# OpAmp.net
KiCad netlist of a schematic drawn in Altium Designer
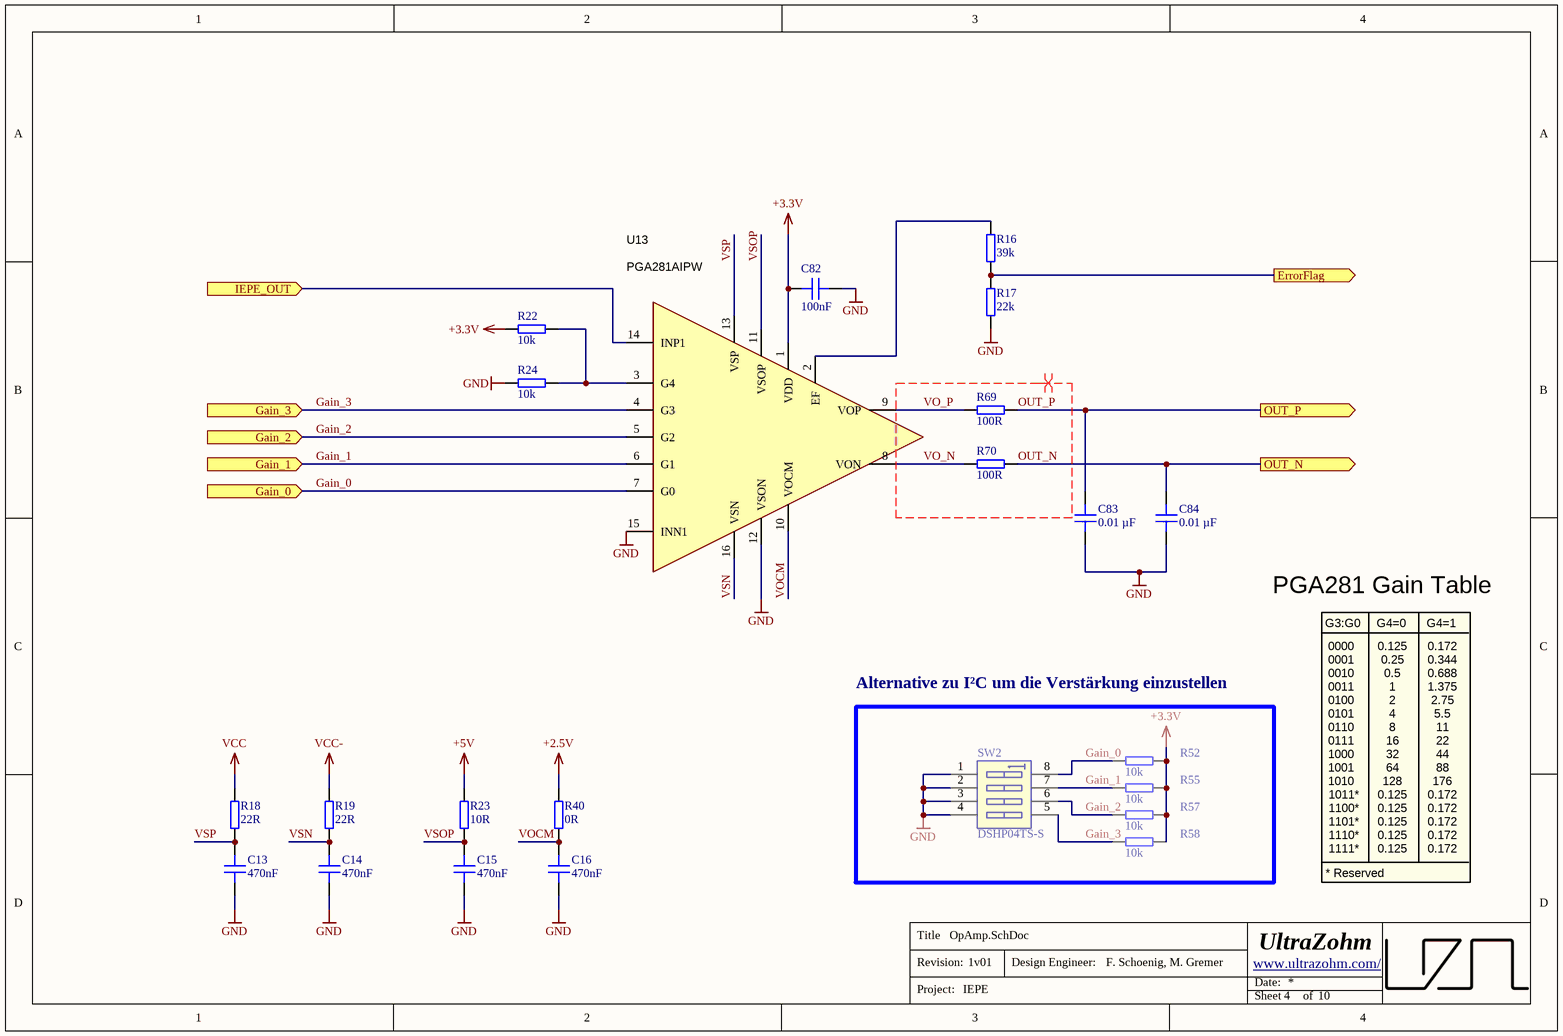
[diagram p0: OpAmp.SchDoc]

(export (version "E")
  (design (tool "Eeschema 10.0.6"))
  (components
    (comp (ref "C13")
      (value "470nF")
      (footprint "C_0603")
      (description "Capacitor 0603, 25 VDC, 0.1 µF, X7R")
      (fields (field (name "MANUFACTURER PART NUMBER") "C0603C104J3REC7411"))
      (libsource (lib "user") (part "Capacitor"))
    )
    (comp (ref "C14")
      (value "470nF")
      (footprint "C_0603")
      (description "Capacitor 0603, 25 VDC, 0.1 µF, X7R")
      (fields (field (name "MANUFACTURER PART NUMBER") "C0603C104J3REC7411"))
      (libsource (lib "user") (part "Capacitor"))
    )
    (comp (ref "C15")
      (value "470nF")
      (footprint "C_0603")
      (description "Capacitor 0603, 25 VDC, 0.1 µF, X7R")
      (fields (field (name "MANUFACTURER PART NUMBER") "C0603C104J3REC7411"))
      (libsource (lib "user") (part "Capacitor"))
    )
    (comp (ref "C16")
      (value "470nF")
      (footprint "C_0603")
      (description "Capacitor 0603, 25 VDC, 0.1 µF, X7R")
      (fields (field (name "MANUFACTURER PART NUMBER") "C0603C104J3REC7411"))
      (libsource (lib "user") (part "Capacitor"))
    )
    (comp (ref "C82")
      (value "100nF")
      (footprint "C_0603")
      (description "Capacitor 0603, 25 VDC, 0.1 µF, X7R")
      (fields (field (name "MANUFACTURER PART NUMBER") "C0603C104J3REC7411"))
      (libsource (lib "user") (part "Capacitor"))
    )
    (comp (ref "C83")
      (value "0.01 µF")
      (footprint "C_0603")
      (description "Capacitor 0603, 50 VDC, 0.01 µF, X7R")
      (fields
        (field (name "MANUFACTURER PART NUMBER") "GCJ188R71H103KA01D")
        (field (name "MANUFACTURER") "muRata")
        (field (name "CREATED FROM") "MGremer")
      )
      (libsource (lib "user") (part "Capacitor"))
    )
    (comp (ref "C84")
      (value "0.01 µF")
      (footprint "C_0603")
      (description "Capacitor 0603, 50 VDC, 0.01 µF, X7R")
      (fields
        (field (name "MANUFACTURER PART NUMBER") "GCJ188R71H103KA01D")
        (field (name "MANUFACTURER") "muRata")
        (field (name "CREATED FROM") "MGremer")
      )
      (libsource (lib "user") (part "Capacitor"))
    )
    (comp (ref "R16")
      (value "39k")
      (footprint "RES 0603_1608")
      (description "SMD resistor E24 series")
      (fields
        (field (name "MANUFACTURER PART NUMBER") "RK73B1JTTDD393J")
        (field (name "MANUFACTURER") "KOA Speer")
        (field (name "CREATED FROM") "MGremer")
      )
      (libsource (lib "user") (part "Resistor"))
    )
    (comp (ref "R17")
      (value "22k")
      (footprint "RES 0603_1608")
      (description "SMD resistor E24 series")
      (fields
        (field (name "MANUFACTURER PART NUMBER") "RK73B1JTTD223J")
        (field (name "MANUFACTURER") "KOA Speer")
        (field (name "CREATED FROM") "MGremer")
      )
      (libsource (lib "user") (part "Resistor"))
    )
    (comp (ref "R18")
      (value "22R")
      (footprint "RES 0603_1608")
      (description "SMD resistor E24 series")
      (fields (field (name "MANUFACTURER PART NUMBER") "RC0603JR-070RL"))
      (libsource (lib "user") (part "Resistor"))
    )
    (comp (ref "R19")
      (value "22R")
      (footprint "RES 0603_1608")
      (description "SMD resistor E24 series")
      (fields (field (name "MANUFACTURER PART NUMBER") "RC0603JR-070RL"))
      (libsource (lib "user") (part "Resistor"))
    )
    (comp (ref "R22")
      (value "10k")
      (footprint "RES 0603_1608")
      (description "SMD resistor E24 series")
      (fields
        (field (name "MANUFACTURER PART NUMBER") "RK73B1JTTD103J")
        (field (name "MANUFACTURER") "KOA Speer")
        (field (name "CREATED FROM") "MGremer")
      )
      (libsource (lib "user") (part "Resistor"))
    )
    (comp (ref "R23")
      (value "10R")
      (footprint "RES 0603_1608")
      (description "SMD resistor E24 series")
      (fields (field (name "MANUFACTURER PART NUMBER") "RC0603JR-070RL"))
      (libsource (lib "user") (part "Resistor"))
    )
    (comp (ref "R24")
      (value "10k")
      (footprint "RES 0603_1608")
      (description "SMD resistor E24 series")
      (fields
        (field (name "MANUFACTURER PART NUMBER") "RK73B1JTTD103J")
        (field (name "MANUFACTURER") "KOA Speer")
        (field (name "CREATED FROM") "MGremer")
      )
      (libsource (lib "user") (part "Resistor"))
    )
    (comp (ref "R40")
      (value "0R")
      (footprint "RES 0603_1608")
      (description "SMD resistor E24 series")
      (fields
        (field (name "MANUFACTURER PART NUMBER") "RC0603JR-070RL")
        (field (name "MANUFACTURER") "YAGEO")
        (field (name "CREATED FROM") "MGremer")
      )
      (libsource (lib "user") (part "Resistor"))
    )
    (comp (ref "R52")
      (value "10k")
      (footprint "RES 0603_1608")
      (description "SMD resistor E24 series")
      (fields
        (field (name "MANUFACTURER PART NUMBER") "RK73B1JTTD103J")
        (field (name "MANUFACTURER") "KOA Speer")
        (field (name "CREATED FROM") "MGremer")
      )
      (libsource (lib "user") (part "Resistor"))
    )
    (comp (ref "R55")
      (value "10k")
      (footprint "RES 0603_1608")
      (description "SMD resistor E24 series")
      (fields
        (field (name "MANUFACTURER PART NUMBER") "RK73B1JTTD103J")
        (field (name "MANUFACTURER") "KOA Speer")
        (field (name "CREATED FROM") "MGremer")
      )
      (libsource (lib "user") (part "Resistor"))
    )
    (comp (ref "R57")
      (value "10k")
      (footprint "RES 0603_1608")
      (description "SMD resistor E24 series")
      (fields
        (field (name "MANUFACTURER PART NUMBER") "RK73B1JTTD103J")
        (field (name "MANUFACTURER") "KOA Speer")
        (field (name "CREATED FROM") "MGremer")
      )
      (libsource (lib "user") (part "Resistor"))
    )
    (comp (ref "R58")
      (value "10k")
      (footprint "RES 0603_1608")
      (description "SMD resistor E24 series")
      (fields
        (field (name "MANUFACTURER PART NUMBER") "RK73B1JTTD103J")
        (field (name "MANUFACTURER") "KOA Speer")
        (field (name "CREATED FROM") "MGremer")
      )
      (libsource (lib "user") (part "Resistor"))
    )
    (comp (ref "R69")
      (value "100R")
      (footprint "RES 0603_1608")
      (description "SMD resistor E24 series")
      (fields
        (field (name "MANUFACTURER PART NUMBER") "RK73B1JTTD101J")
        (field (name "MANUFACTURER") "KOA Speer")
        (field (name "CREATED FROM") "MGremer")
      )
      (libsource (lib "user") (part "Resistor"))
    )
    (comp (ref "R70")
      (value "100R")
      (footprint "RES 0603_1608")
      (description "SMD resistor E24 series")
      (fields
        (field (name "MANUFACTURER PART NUMBER") "RK73B1JTTD101J")
        (field (name "MANUFACTURER") "KOA Speer")
        (field (name "CREATED FROM") "MGremer")
      )
      (libsource (lib "user") (part "Resistor"))
    )
    (comp (ref "SW2")
      (value "DSHP04TS-S")
      (footprint "416131160804")
      (description "04p, 1.27mm Pitch, Horizontal, HP Type, SMT, flat Actuator, black, with Tape, T&R")
      (fields
        (field (name "MANUFACTURER") "XKB Connectivity")
        (field (name "LCSC PART NUMBER") "C319050")
        (field (name "CREATED FROM") "T. Wendt")
      )
      (libsource (lib "user") (part "DIP-SW-4p"))
    )
    (comp (ref "U13")
      (value "PGA281AIPW")
      (footprint "PW0016A_N")
      (description "Precision,Zero-Drift,High-Voltage,Programmable Gain Instrumentation Amplifier")
      (fields
        (field (name "MANUFACTURER") "Texas Instruments")
        (field (name "PARTNUMBER") "Used in BOM report")
        (field (name "SYMBOLCREATOR") "Use a-id")
        (field (name "CREATED FROM") "PTurowski")
      )
      (libsource (lib "user") (part "PGA281"))
    )
  )
  (nets
    (net (code "1") (name "+2.5V") (class "Default")
      (node (ref "R40") (pin "2") (pinfunction "2_2") (pintype "passive"))
    )
    (net (code "2") (name "+3.3V") (class "Default")
      (node (ref "C82") (pin "2") (pinfunction "2_2") (pintype "passive"))
      (node (ref "R22") (pin "1") (pinfunction "1_1") (pintype "passive"))
      (node (ref "R52") (pin "1") (pinfunction "1_1") (pintype "passive"))
      (node (ref "R55") (pin "1") (pinfunction "1_1") (pintype "passive"))
      (node (ref "R57") (pin "1") (pinfunction "1_1") (pintype "passive"))
      (node (ref "R58") (pin "1") (pinfunction "1_1") (pintype "passive"))
      (node (ref "U13") (pin "1") (pinfunction "VDD_1") (pintype "passive"))
    )
    (net (code "3") (name "+5V") (class "Default")
      (node (ref "R23") (pin "2") (pinfunction "2_2") (pintype "passive"))
    )
    (net (code "4") (name "/ErrorFlag") (class "Default")
      (node (ref "R16") (pin "1") (pinfunction "1_1") (pintype "passive"))
      (node (ref "R17") (pin "2") (pinfunction "2_2") (pintype "passive"))
    )
    (net (code "5") (name "/Gain_0") (class "Default")
      (node (ref "R52") (pin "2") (pinfunction "2_2") (pintype "passive"))
      (node (ref "SW2") (pin "8") (pinfunction "8_8") (pintype "passive"))
      (node (ref "U13") (pin "7") (pinfunction "G0_7") (pintype "passive"))
    )
    (net (code "6") (name "/Gain_1") (class "Default")
      (node (ref "R55") (pin "2") (pinfunction "2_2") (pintype "passive"))
      (node (ref "SW2") (pin "7") (pinfunction "7_7") (pintype "passive"))
      (node (ref "U13") (pin "6") (pinfunction "G1_6") (pintype "passive"))
    )
    (net (code "7") (name "/Gain_2") (class "Default")
      (node (ref "R57") (pin "2") (pinfunction "2_2") (pintype "passive"))
      (node (ref "SW2") (pin "6") (pinfunction "6_6") (pintype "passive"))
      (node (ref "U13") (pin "5") (pinfunction "G2_5") (pintype "passive"))
    )
    (net (code "8") (name "/Gain_3") (class "Default")
      (node (ref "R58") (pin "2") (pinfunction "2_2") (pintype "passive"))
      (node (ref "SW2") (pin "5") (pinfunction "5_5") (pintype "passive"))
      (node (ref "U13") (pin "4") (pinfunction "G3_4") (pintype "passive"))
    )
    (net (code "9") (name "/IEPE_OUT") (class "Default")
      (node (ref "U13") (pin "14") (pinfunction "INP1_14") (pintype "passive"))
    )
    (net (code "10") (name "/OUT_N") (class "Default")
      (node (ref "C84") (pin "2") (pinfunction "2_2") (pintype "passive"))
      (node (ref "R70") (pin "2") (pinfunction "2_2") (pintype "passive"))
    )
    (net (code "11") (name "/OUT_P") (class "Default")
      (node (ref "C83") (pin "2") (pinfunction "2_2") (pintype "passive"))
      (node (ref "R69") (pin "2") (pinfunction "2_2") (pintype "passive"))
    )
    (net (code "12") (name "/VOCM") (class "Default")
      (node (ref "C16") (pin "2") (pinfunction "2_2") (pintype "passive"))
      (node (ref "R40") (pin "1") (pinfunction "1_1") (pintype "passive"))
      (node (ref "U13") (pin "10") (pinfunction "VOCM_10") (pintype "passive"))
    )
    (net (code "13") (name "/VO_N") (class "Default")
      (node (ref "R70") (pin "1") (pinfunction "1_1") (pintype "passive"))
      (node (ref "U13") (pin "8") (pinfunction "VON_8") (pintype "passive"))
    )
    (net (code "14") (name "/VO_P") (class "Default")
      (node (ref "R69") (pin "1") (pinfunction "1_1") (pintype "passive"))
      (node (ref "U13") (pin "9") (pinfunction "VOP_9") (pintype "passive"))
    )
    (net (code "15") (name "/VSN") (class "Default")
      (node (ref "C14") (pin "2") (pinfunction "2_2") (pintype "passive"))
      (node (ref "R19") (pin "1") (pinfunction "1_1") (pintype "passive"))
      (node (ref "U13") (pin "16") (pinfunction "VSN_16") (pintype "passive"))
    )
    (net (code "16") (name "/VSOP") (class "Default")
      (node (ref "C15") (pin "2") (pinfunction "2_2") (pintype "passive"))
      (node (ref "R23") (pin "1") (pinfunction "1_1") (pintype "passive"))
      (node (ref "U13") (pin "11") (pinfunction "VSOP_11") (pintype "passive"))
    )
    (net (code "17") (name "/VSP") (class "Default")
      (node (ref "C13") (pin "2") (pinfunction "2_2") (pintype "passive"))
      (node (ref "R18") (pin "1") (pinfunction "1_1") (pintype "passive"))
      (node (ref "U13") (pin "13") (pinfunction "VSP_13") (pintype "passive"))
    )
    (net (code "18") (name "GND") (class "Default")
      (node (ref "C13") (pin "1") (pinfunction "1_1") (pintype "passive"))
      (node (ref "C14") (pin "1") (pinfunction "1_1") (pintype "passive"))
      (node (ref "C15") (pin "1") (pinfunction "1_1") (pintype "passive"))
      (node (ref "C16") (pin "1") (pinfunction "1_1") (pintype "passive"))
      (node (ref "C82") (pin "1") (pinfunction "1_1") (pintype "passive"))
      (node (ref "C83") (pin "1") (pinfunction "1_1") (pintype "passive"))
      (node (ref "C84") (pin "1") (pinfunction "1_1") (pintype "passive"))
      (node (ref "R17") (pin "1") (pinfunction "1_1") (pintype "passive"))
      (node (ref "R24") (pin "1") (pinfunction "1_1") (pintype "passive"))
      (node (ref "SW2") (pin "1") (pinfunction "1_1") (pintype "passive"))
      (node (ref "SW2") (pin "2") (pinfunction "2_2") (pintype "passive"))
      (node (ref "SW2") (pin "3") (pinfunction "3_3") (pintype "passive"))
      (node (ref "SW2") (pin "4") (pinfunction "4_4") (pintype "passive"))
      (node (ref "U13") (pin "12") (pinfunction "VSON_12") (pintype "passive"))
      (node (ref "U13") (pin "15") (pinfunction "INN1_15") (pintype "passive"))
    )
    (net (code "19") (name "Net-(U13-EF)") (class "Default")
      (node (ref "R16") (pin "2") (pinfunction "2_2") (pintype "passive"))
      (node (ref "U13") (pin "2") (pinfunction "EF_2") (pintype "passive"))
    )
    (net (code "20") (name "Net-(U13-G4)") (class "Default")
      (node (ref "R22") (pin "2") (pinfunction "2_2") (pintype "passive"))
      (node (ref "R24") (pin "2") (pinfunction "2_2") (pintype "passive"))
      (node (ref "U13") (pin "3") (pinfunction "G4_3") (pintype "passive"))
    )
    (net (code "21") (name "VCC") (class "Default")
      (node (ref "R18") (pin "2") (pinfunction "2_2") (pintype "passive"))
    )
    (net (code "22") (name "VCC-") (class "Default")
      (node (ref "R19") (pin "2") (pinfunction "2_2") (pintype "passive"))
    )
  )
)
